# openSX70_CAKE_V35_20180116_manually-rout.net
KiCad netlist of a schematic drawn in EAGLE
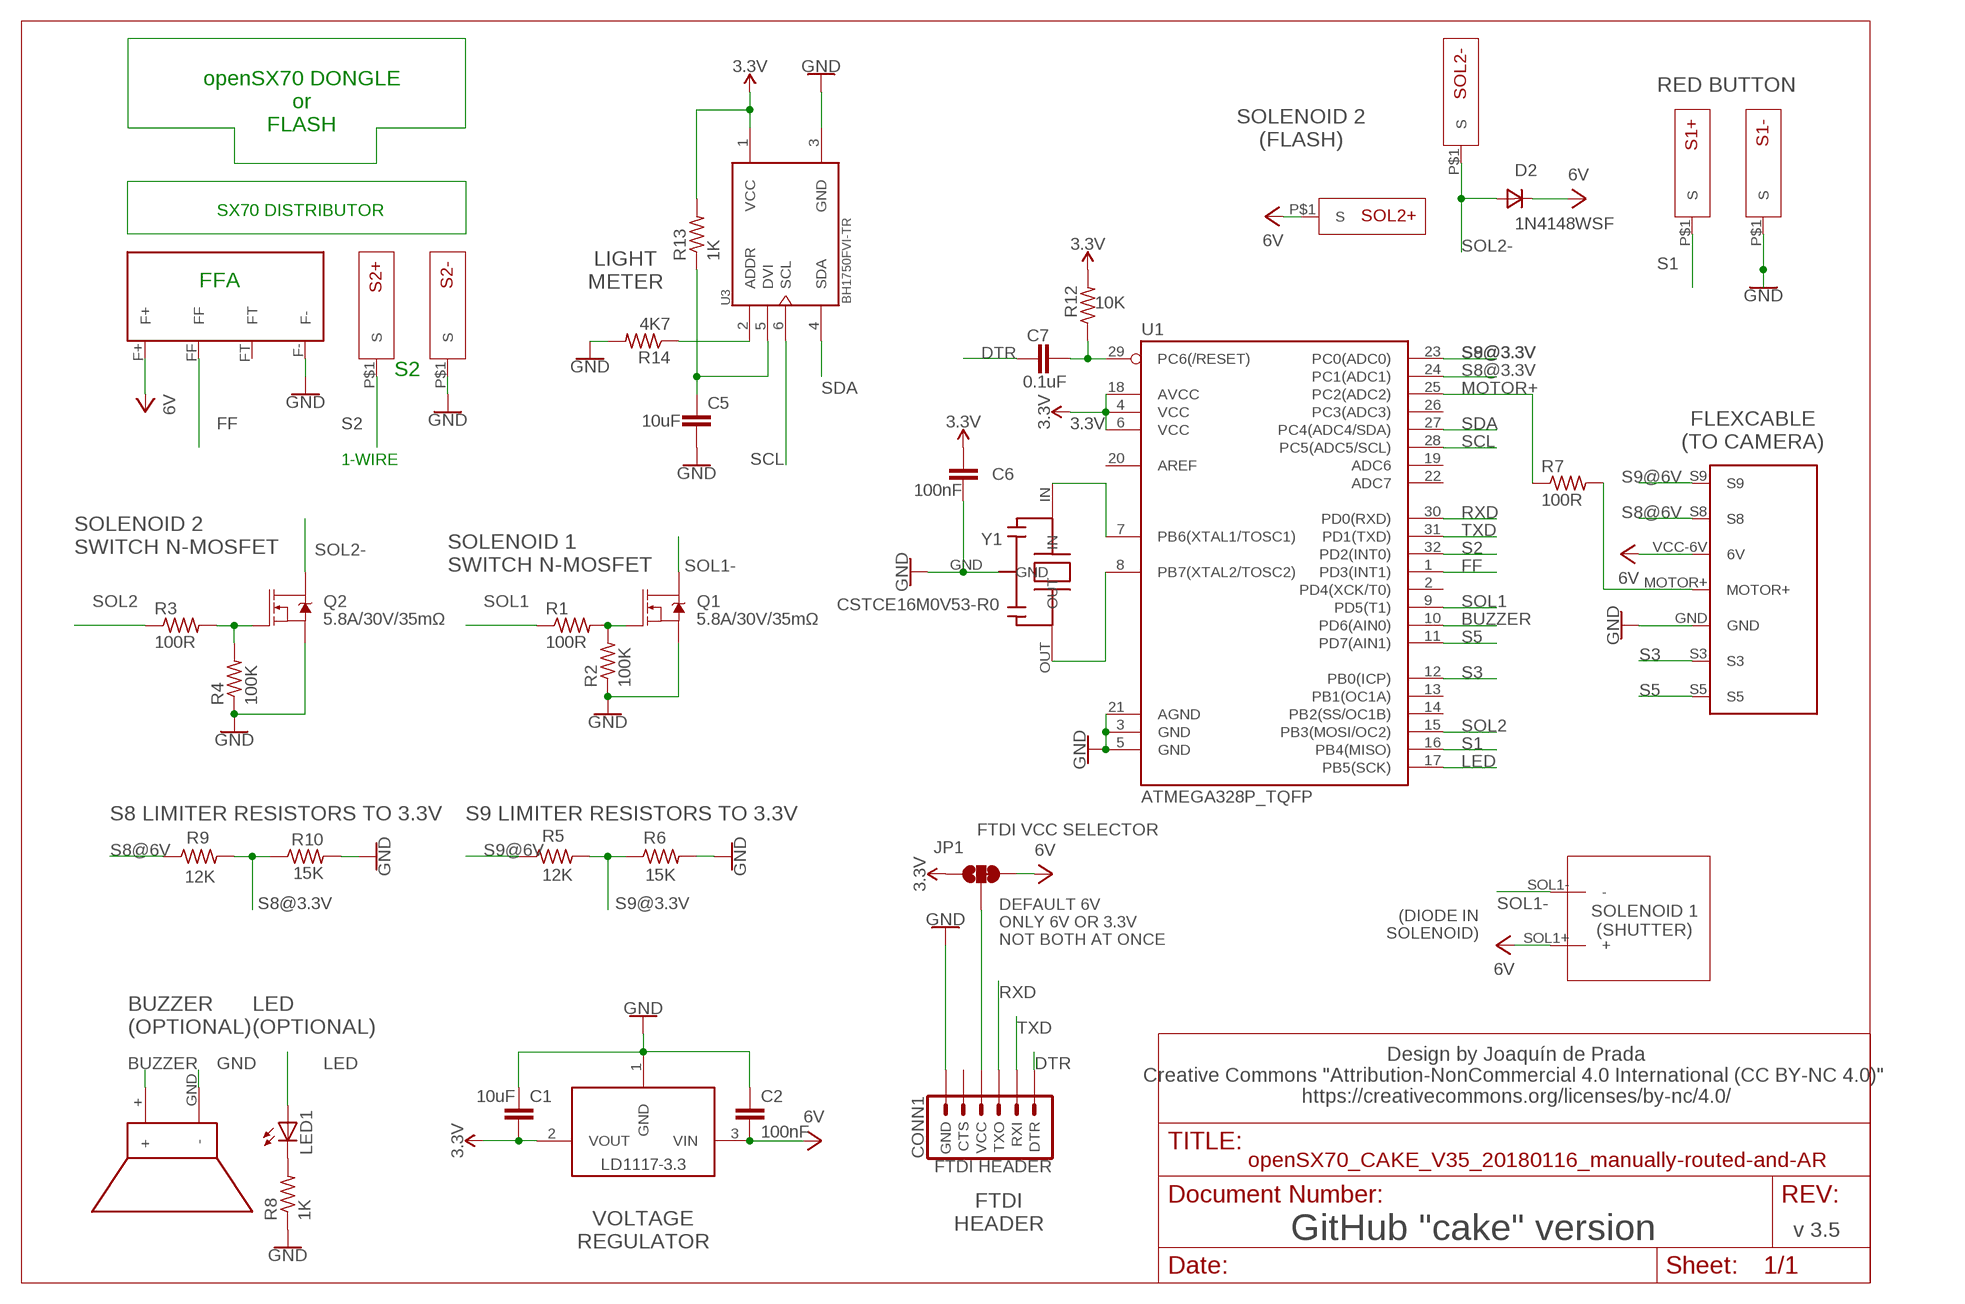
[diagram p0: schematic, sheet 1]

(export (version "E")
  (design (tool "Eeschema 10.0.6"))
  (components
    (comp (ref "BUZZ1")
      (value "CSET8-5G")
      (footprint "eagle-import:CSET8-5G_PACKAGE")
      (libsource (lib "eagle-import") (part "CSET8-5G"))
    )
    (comp (ref "C1")
      (value "10uF")
      (footprint "eagle-import:0603")
      (libsource (lib "eagle-import") (part "10UF-0603-6.3V-20%"))
    )
    (comp (ref "C2")
      (value "100nF")
      (footprint "eagle-import:C0603K")
      (libsource (lib "eagle-import") (part "C-EUC0603K"))
    )
    (comp (ref "C5")
      (value "10uF")
      (footprint "eagle-import:0603")
      (libsource (lib "eagle-import") (part "10UF-0603-6.3V-20%"))
    )
    (comp (ref "C6")
      (value "100nF")
      (footprint "eagle-import:C0805")
      (libsource (lib "eagle-import") (part "resistor_C-EUC0805"))
    )
    (comp (ref "C7")
      (value "0.1uF")
      (footprint "eagle-import:0603")
      (libsource (lib "eagle-import") (part "0.1UF-0603-25V-(+80/-20%)"))
    )
    (comp (ref "CONN1")
      (value "FTDI HEADER")
      (footprint "eagle-import:1X06")
      (libsource (lib "eagle-import") (part "6_PIN_SERIAL_TARGET"))
    )
    (comp (ref "D2")
      (value "1N4148WSF")
      (footprint "eagle-import:SOD323")
      (fields (field (name "MPN") "CDSOD323-T05C"))
      (libsource (lib "eagle-import") (part "DSOD323"))
    )
    (comp (ref "JP1")
      (value "FTDI VCC SELECTOR")
      (footprint "eagle-import:SMT-JUMPER_3_1-NC_TRACE_SILK")
      (libsource (lib "eagle-import") (part "JUMPER-SMT_3_1-NC_TRACE_SILK"))
    )
    (comp (ref "LD11173.3V")
      (value "LD1117 3.3V")
      (footprint "eagle-import:SOT223")
      (fields (field (name "MF") "Advanced Monolithic Systems") (field (name "MP") "AMS1117-5.0"))
      (libsource (lib "eagle-import") (part "LD1117-3.3"))
    )
    (comp (ref "LED1")
      (value "LEDCHIPLED_0805")
      (footprint "eagle-import:CHIPLED_0805")
      (libsource (lib "eagle-import") (part "LEDCHIPLED_0805"))
    )
    (comp (ref "Q1")
      (value "5.8A/30V/35mΩ")
      (footprint "eagle-import:SOT23-3")
      (libsource (lib "eagle-import") (part "MOSFET-NCH-AO3404A"))
    )
    (comp (ref "Q2")
      (value "5.8A/30V/35mΩ")
      (footprint "eagle-import:SOT23-3")
      (libsource (lib "eagle-import") (part "MOSFET-NCH-AO3404A"))
    )
    (comp (ref "R1")
      (value "100R")
      (footprint "eagle-import:R0603")
      (libsource (lib "eagle-import") (part "R-US_R0603"))
    )
    (comp (ref "R2")
      (value "100K")
      (footprint "eagle-import:R0603")
      (libsource (lib "eagle-import") (part "R-US_R0603"))
    )
    (comp (ref "R3")
      (value "100R")
      (footprint "eagle-import:R0603")
      (libsource (lib "eagle-import") (part "R-US_R0603"))
    )
    (comp (ref "R4")
      (value "100K")
      (footprint "eagle-import:R0603")
      (libsource (lib "eagle-import") (part "R-US_R0603"))
    )
    (comp (ref "R5")
      (value "12K")
      (footprint "eagle-import:R0603")
      (libsource (lib "eagle-import") (part "R-US_R0603"))
    )
    (comp (ref "R6")
      (value "15K")
      (footprint "eagle-import:R0603")
      (libsource (lib "eagle-import") (part "R-US_R0603"))
    )
    (comp (ref "R7")
      (value "100R")
      (footprint "eagle-import:R0603")
      (libsource (lib "eagle-import") (part "R-US_R0603"))
    )
    (comp (ref "R8")
      (value "1K")
      (footprint "eagle-import:R0603")
      (libsource (lib "eagle-import") (part "R-US_R0603"))
    )
    (comp (ref "R9")
      (value "12K")
      (footprint "eagle-import:R0603")
      (libsource (lib "eagle-import") (part "R-US_R0603"))
    )
    (comp (ref "R10")
      (value "15K")
      (footprint "eagle-import:R0603")
      (libsource (lib "eagle-import") (part "R-US_R0603"))
    )
    (comp (ref "R12")
      (value "10K")
      (footprint "eagle-import:R0603")
      (libsource (lib "eagle-import") (part "R-US_R0603"))
    )
    (comp (ref "R13")
      (value "1K")
      (footprint "eagle-import:R0603")
      (libsource (lib "eagle-import") (part "R-US_R0603"))
    )
    (comp (ref "R14")
      (value "4K7")
      (footprint "eagle-import:R0603")
      (libsource (lib "eagle-import") (part "R-US_R0603"))
    )
    (comp (ref "S1+")
      (value "SX70-S-PAD-NEW")
      (footprint "eagle-import:SX70-S-PAD2")
      (libsource (lib "eagle-import") (part "SX70-S-PAD-NEW"))
    )
    (comp (ref "S1-")
      (value "SX70-S-PAD-NEW")
      (footprint "eagle-import:SX70-S-PAD2")
      (libsource (lib "eagle-import") (part "SX70-S-PAD-NEW"))
    )
    (comp (ref "S2+")
      (value "SX70-S-PAD-NEW")
      (footprint "eagle-import:SX70-S-PAD2")
      (libsource (lib "eagle-import") (part "SX70-S-PAD-NEW"))
    )
    (comp (ref "S2-")
      (value "SX70-S-PAD-NEW")
      (footprint "eagle-import:SX70-S-PAD2")
      (libsource (lib "eagle-import") (part "SX70-S-PAD-NEW"))
    )
    (comp (ref "SOL1")
      (value "SX70-SOLENOID1-2PADS")
      (footprint "eagle-import:SX70-SOLENOID1-2")
      (libsource (lib "eagle-import") (part "SX70-SOLENOID1-2PADS"))
    )
    (comp (ref "SOL2+")
      (value "SX70-S-PAD-NEW")
      (footprint "eagle-import:SX70-S-PAD2")
      (libsource (lib "eagle-import") (part "SX70-S-PAD-NEW"))
    )
    (comp (ref "SOL2-")
      (value "SX70-S-PAD-NEW")
      (footprint "eagle-import:SX70-S-PAD2")
      (libsource (lib "eagle-import") (part "SX70-S-PAD-NEW"))
    )
    (comp (ref "U$1")
      (value "SX70-7-PAD")
      (footprint "eagle-import:SX70-7-PAD")
      (libsource (lib "eagle-import") (part "SX70-7-PAD"))
    )
    (comp (ref "U$2")
      (value "FFA")
      (footprint "eagle-import:FFA-PAD-PACKAGE")
      (libsource (lib "eagle-import") (part "SX70-FFA-PAD"))
    )
    (comp (ref "U1")
      (value "ATMEGA328P_TQFP")
      (footprint "eagle-import:TQFP32-08")
      (libsource (lib "eagle-import") (part "ATMEGA328P_TQFP"))
    )
    (comp (ref "U3")
      (value "BH1750FVI-TR")
      (footprint "eagle-import:SOTFL50P300X75-6N")
      (fields (field (name "MF") "Rohm"))
      (libsource (lib "eagle-import") (part "BH1750FVI-TR"))
    )
    (comp (ref "Y1")
      (value "CSTCE16M0V53-R0")
      (footprint "eagle-import:CFP95P160X100-3N")
      (fields (field (name "MF") "Murata"))
      (libsource (lib "eagle-import") (part "CSTCE16M0V53-R0"))
    )
  )
  (nets
    (net (code "1") (name "/BUZZER") (class "Default")
      (node (ref "BUZZ1") (pin "+") (pinfunction "+_+") (pintype "bidirectional"))
      (node (ref "U1") (pin "10") (pinfunction "PD6(AIN0)_10") (pintype "bidirectional"))
    )
    (net (code "2") (name "/DTR") (class "Default")
      (node (ref "C7") (pin "1") (pinfunction "1_1") (pintype "passive"))
      (node (ref "CONN1") (pin "1") (pinfunction "DTR_1") (pintype "passive"))
    )
    (net (code "3") (name "/FF") (class "Default")
      (node (ref "U$2") (pin "FF") (pinfunction "FF_FF") (pintype "bidirectional"))
      (node (ref "U1") (pin "1") (pinfunction "PD3(INT1)_1") (pintype "bidirectional"))
    )
    (net (code "4") (name "/LED") (class "Default")
      (node (ref "LED1") (pin "A") (pinfunction "A_A") (pintype "passive"))
      (node (ref "U1") (pin "17") (pinfunction "PB5(SCK)_17") (pintype "bidirectional"))
    )
    (net (code "5") (name "/MOTOR+") (class "Default")
      (node (ref "R7") (pin "1") (pinfunction "1_1") (pintype "passive"))
      (node (ref "U1") (pin "25") (pinfunction "PC2(ADC2)_25") (pintype "bidirectional"))
    )
    (net (code "6") (name "/RXD") (class "Default")
      (node (ref "CONN1") (pin "3") (pinfunction "TXO_3") (pintype "passive"))
      (node (ref "U1") (pin "30") (pinfunction "PD0(RXD)_30") (pintype "bidirectional"))
    )
    (net (code "7") (name "/S1") (class "Default")
      (node (ref "S1+") (pin "P$1") (pinfunction "S_P$1") (pintype "bidirectional"))
      (node (ref "U1") (pin "16") (pinfunction "PB4(MISO)_16") (pintype "bidirectional"))
    )
    (net (code "8") (name "/S2") (class "Default")
      (node (ref "S2+") (pin "P$1") (pinfunction "S_P$1") (pintype "bidirectional"))
      (node (ref "U1") (pin "32") (pinfunction "PD2(INT0)_32") (pintype "bidirectional"))
    )
    (net (code "9") (name "/S3") (class "Default")
      (node (ref "U$1") (pin "S3") (pinfunction "S3_S3") (pintype "bidirectional"))
      (node (ref "U1") (pin "12") (pinfunction "PB0(ICP)_12") (pintype "bidirectional"))
    )
    (net (code "10") (name "/S5") (class "Default")
      (node (ref "U$1") (pin "S5") (pinfunction "S5_S5") (pintype "bidirectional"))
      (node (ref "U1") (pin "11") (pinfunction "PD7(AIN1)_11") (pintype "bidirectional"))
    )
    (net (code "11") (name "/S8@3.3V") (class "Default")
      (node (ref "R10") (pin "1") (pinfunction "1_1") (pintype "passive"))
      (node (ref "R9") (pin "2") (pinfunction "2_2") (pintype "passive"))
      (node (ref "U1") (pin "24") (pinfunction "PC1(ADC1)_24") (pintype "bidirectional"))
    )
    (net (code "12") (name "/S8@6V") (class "Default")
      (node (ref "R9") (pin "1") (pinfunction "1_1") (pintype "passive"))
      (node (ref "U$1") (pin "S8") (pinfunction "S8_S8") (pintype "bidirectional"))
    )
    (net (code "13") (name "/S9@3.3V") (class "Default")
      (node (ref "R5") (pin "2") (pinfunction "2_2") (pintype "passive"))
      (node (ref "R6") (pin "1") (pinfunction "1_1") (pintype "passive"))
      (node (ref "U1") (pin "23") (pinfunction "PC0(ADC0)_23") (pintype "bidirectional"))
    )
    (net (code "14") (name "/S9@6V") (class "Default")
      (node (ref "R5") (pin "1") (pinfunction "1_1") (pintype "passive"))
      (node (ref "U$1") (pin "S9") (pinfunction "S9_S9") (pintype "bidirectional"))
    )
    (net (code "15") (name "/SCL") (class "Default")
      (node (ref "U1") (pin "28") (pinfunction "PC5(ADC5/SCL)_28") (pintype "bidirectional"))
      (node (ref "U3") (pin "6") (pinfunction "SCL_6") (pintype "input"))
    )
    (net (code "16") (name "/SDA") (class "Default")
      (node (ref "U1") (pin "27") (pinfunction "PC4(ADC4/SDA)_27") (pintype "bidirectional"))
      (node (ref "U3") (pin "4") (pinfunction "SDA_4") (pintype "bidirectional"))
    )
    (net (code "17") (name "/SOL1") (class "Default")
      (node (ref "R1") (pin "1") (pinfunction "1_1") (pintype "passive"))
      (node (ref "U1") (pin "9") (pinfunction "PD5(T1)_9") (pintype "bidirectional"))
    )
    (net (code "18") (name "/SOL1-") (class "Default")
      (node (ref "Q1") (pin "3") (pinfunction "D_3") (pintype "bidirectional"))
      (node (ref "SOL1") (pin "SOL1-") (pinfunction "-_SOL1-") (pintype "bidirectional"))
    )
    (net (code "19") (name "/SOL2") (class "Default")
      (node (ref "R3") (pin "1") (pinfunction "1_1") (pintype "passive"))
      (node (ref "U1") (pin "15") (pinfunction "PB3(MOSI/OC2)_15") (pintype "bidirectional"))
    )
    (net (code "20") (name "/SOL2-") (class "Default")
      (node (ref "D2") (pin "2") (pinfunction "A_2") (pintype "passive"))
      (node (ref "Q2") (pin "3") (pinfunction "D_3") (pintype "bidirectional"))
      (node (ref "SOL2-") (pin "P$1") (pinfunction "S_P$1") (pintype "bidirectional"))
    )
    (net (code "21") (name "/TXD") (class "Default")
      (node (ref "CONN1") (pin "2") (pinfunction "RXI_2") (pintype "passive"))
      (node (ref "U1") (pin "31") (pinfunction "PD1(TXD)_31") (pintype "bidirectional"))
    )
    (net (code "22") (name "3.3V") (class "Default")
      (node (ref "C1") (pin "2") (pinfunction "2_2") (pintype "passive"))
      (node (ref "C6") (pin "1") (pinfunction "1_1") (pintype "passive"))
      (node (ref "JP1") (pin "1") (pinfunction "1_1") (pintype "passive"))
      (node (ref "LD11173.3V") (pin "2") (pinfunction "VOUT_2") (pintype "bidirectional"))
      (node (ref "R12") (pin "2") (pinfunction "2_2") (pintype "passive"))
      (node (ref "R13") (pin "2") (pinfunction "2_2") (pintype "passive"))
      (node (ref "U1") (pin "18") (pinfunction "AVCC_18") (pintype "bidirectional"))
      (node (ref "U1") (pin "4") (pinfunction "VCC_4") (pintype "bidirectional"))
      (node (ref "U1") (pin "6") (pinfunction "VCC_6") (pintype "bidirectional"))
      (node (ref "U3") (pin "1") (pinfunction "VCC_1") (pintype "power_in"))
    )
    (net (code "23") (name "6V") (class "Default")
      (node (ref "C2") (pin "2") (pinfunction "2_2") (pintype "passive"))
      (node (ref "D2") (pin "1") (pinfunction "C_1") (pintype "passive"))
      (node (ref "JP1") (pin "3") (pinfunction "3_3") (pintype "passive"))
      (node (ref "LD11173.3V") (pin "3") (pinfunction "VIN_3") (pintype "bidirectional"))
      (node (ref "SOL1") (pin "SOL1+") (pinfunction "+_SOL1+") (pintype "bidirectional"))
      (node (ref "SOL2+") (pin "P$1") (pinfunction "S_P$1") (pintype "bidirectional"))
      (node (ref "U$1") (pin "VCC-6V") (pinfunction "6V_VCC-6V") (pintype "bidirectional"))
      (node (ref "U$2") (pin "F+") (pinfunction "F+_F+") (pintype "bidirectional"))
    )
    (net (code "24") (name "GND") (class "Default")
      (node (ref "BUZZ1") (pin "GND") (pinfunction "-_GND") (pintype "bidirectional"))
      (node (ref "C1") (pin "1") (pinfunction "1_1") (pintype "passive"))
      (node (ref "C2") (pin "1") (pinfunction "1_1") (pintype "passive"))
      (node (ref "C5") (pin "2") (pinfunction "2_2") (pintype "passive"))
      (node (ref "C6") (pin "2") (pinfunction "2_2") (pintype "passive"))
      (node (ref "CONN1") (pin "6") (pinfunction "GND_6") (pintype "passive"))
      (node (ref "LD11173.3V") (pin "1") (pinfunction "GND_1") (pintype "bidirectional"))
      (node (ref "Q1") (pin "2") (pinfunction "S_2") (pintype "bidirectional"))
      (node (ref "Q2") (pin "2") (pinfunction "S_2") (pintype "bidirectional"))
      (node (ref "R10") (pin "2") (pinfunction "2_2") (pintype "passive"))
      (node (ref "R14") (pin "2") (pinfunction "2_2") (pintype "passive"))
      (node (ref "R2") (pin "1") (pinfunction "1_1") (pintype "passive"))
      (node (ref "R4") (pin "1") (pinfunction "1_1") (pintype "passive"))
      (node (ref "R6") (pin "2") (pinfunction "2_2") (pintype "passive"))
      (node (ref "R8") (pin "1") (pinfunction "1_1") (pintype "passive"))
      (node (ref "S1-") (pin "P$1") (pinfunction "S_P$1") (pintype "bidirectional"))
      (node (ref "S2-") (pin "P$1") (pinfunction "S_P$1") (pintype "bidirectional"))
      (node (ref "U$1") (pin "GND") (pinfunction "GND_GND") (pintype "bidirectional"))
      (node (ref "U$2") (pin "F-") (pinfunction "F-_F-") (pintype "bidirectional"))
      (node (ref "U1") (pin "21") (pinfunction "AGND_21") (pintype "bidirectional"))
      (node (ref "U1") (pin "3") (pinfunction "GND_3") (pintype "bidirectional"))
      (node (ref "U1") (pin "5") (pinfunction "GND_5") (pintype "bidirectional"))
      (node (ref "U3") (pin "3") (pinfunction "GND_3") (pintype "power_in"))
      (node (ref "Y1") (pin "GND") (pinfunction "GND_GND") (pintype "passive"))
    )
    (net (code "25") (name "Net-(CONN1-VCC)") (class "Default")
      (node (ref "CONN1") (pin "4") (pinfunction "VCC_4") (pintype "passive"))
      (node (ref "JP1") (pin "2") (pinfunction "2_2") (pintype "passive"))
    )
    (net (code "26") (name "Net-(LED1-PadC)") (class "Default")
      (node (ref "LED1") (pin "C") (pinfunction "C_C") (pintype "passive"))
      (node (ref "R8") (pin "2") (pinfunction "2_2") (pintype "passive"))
    )
    (net (code "27") (name "Net-(Q1-G)") (class "Default")
      (node (ref "Q1") (pin "1") (pinfunction "G_1") (pintype "bidirectional"))
      (node (ref "R1") (pin "2") (pinfunction "2_2") (pintype "passive"))
      (node (ref "R2") (pin "2") (pinfunction "2_2") (pintype "passive"))
    )
    (net (code "28") (name "Net-(Q2-G)") (class "Default")
      (node (ref "Q2") (pin "1") (pinfunction "G_1") (pintype "bidirectional"))
      (node (ref "R3") (pin "2") (pinfunction "2_2") (pintype "passive"))
      (node (ref "R4") (pin "2") (pinfunction "2_2") (pintype "passive"))
    )
    (net (code "29") (name "Net-(R7-Pad2)") (class "Default")
      (node (ref "R7") (pin "2") (pinfunction "2_2") (pintype "passive"))
      (node (ref "U$1") (pin "MOTOR+") (pinfunction "MOTOR+_MOTOR+") (pintype "bidirectional"))
    )
    (net (code "30") (name "Net-(U1-PB6(XTAL1{slash}TOSC1))") (class "Default")
      (node (ref "U1") (pin "7") (pinfunction "PB6(XTAL1/TOSC1)_7") (pintype "bidirectional"))
      (node (ref "Y1") (pin "IN") (pinfunction "IN_IN") (pintype "input"))
    )
    (net (code "31") (name "Net-(U1-PB7(XTAL2{slash}TOSC2))") (class "Default")
      (node (ref "U1") (pin "8") (pinfunction "PB7(XTAL2/TOSC2)_8") (pintype "bidirectional"))
      (node (ref "Y1") (pin "OUT") (pinfunction "OUT_OUT") (pintype "output"))
    )
    (net (code "32") (name "Net-(U1-PC6({slash}RESET))") (class "Default")
      (node (ref "C7") (pin "2") (pinfunction "2_2") (pintype "passive"))
      (node (ref "R12") (pin "1") (pinfunction "1_1") (pintype "passive"))
      (node (ref "U1") (pin "29") (pinfunction "PC6(/RESET)_29") (pintype "bidirectional"))
    )
    (net (code "33") (name "Net-(U3-ADDR)") (class "Default")
      (node (ref "R14") (pin "1") (pinfunction "1_1") (pintype "passive"))
      (node (ref "U3") (pin "2") (pinfunction "ADDR_2") (pintype "input"))
    )
    (net (code "34") (name "Net-(U3-DVI)") (class "Default")
      (node (ref "C5") (pin "1") (pinfunction "1_1") (pintype "passive"))
      (node (ref "R13") (pin "1") (pinfunction "1_1") (pintype "passive"))
      (node (ref "U3") (pin "5") (pinfunction "DVI_5") (pintype "input"))
    )
    (net (code "35") (name "unconnected-(CONN1-CTS-Pad5)") (class "Default")
      (node (ref "CONN1") (pin "5") (pinfunction "CTS_5") (pintype "passive"))
    )
    (net (code "36") (name "unconnected-(U$2-PadFT)") (class "Default")
      (node (ref "U$2") (pin "FT") (pinfunction "FT_FT") (pintype "bidirectional"))
    )
    (net (code "37") (name "unconnected-(U1-ADC6-Pad19)") (class "Default")
      (node (ref "U1") (pin "19") (pinfunction "ADC6_19") (pintype "bidirectional"))
    )
    (net (code "38") (name "unconnected-(U1-ADC7-Pad22)") (class "Default")
      (node (ref "U1") (pin "22") (pinfunction "ADC7_22") (pintype "bidirectional"))
    )
    (net (code "39") (name "unconnected-(U1-AREF-Pad20)") (class "Default")
      (node (ref "U1") (pin "20") (pinfunction "AREF_20") (pintype "bidirectional"))
    )
    (net (code "40") (name "unconnected-(U1-PB1(OC1A)-Pad13)") (class "Default")
      (node (ref "U1") (pin "13") (pinfunction "PB1(OC1A)_13") (pintype "bidirectional"))
    )
    (net (code "41") (name "unconnected-(U1-PB2(SS{slash}OC1B)-Pad14)") (class "Default")
      (node (ref "U1") (pin "14") (pinfunction "PB2(SS/OC1B)_14") (pintype "bidirectional"))
    )
    (net (code "42") (name "unconnected-(U1-PC3(ADC3)-Pad26)") (class "Default")
      (node (ref "U1") (pin "26") (pinfunction "PC3(ADC3)_26") (pintype "bidirectional"))
    )
    (net (code "43") (name "unconnected-(U1-PD4(XCK{slash}T0)-Pad2)") (class "Default")
      (node (ref "U1") (pin "2") (pinfunction "PD4(XCK/T0)_2") (pintype "bidirectional"))
    )
  )
)
